# Power.net
KiCad netlist of a schematic drawn in Altium Designer
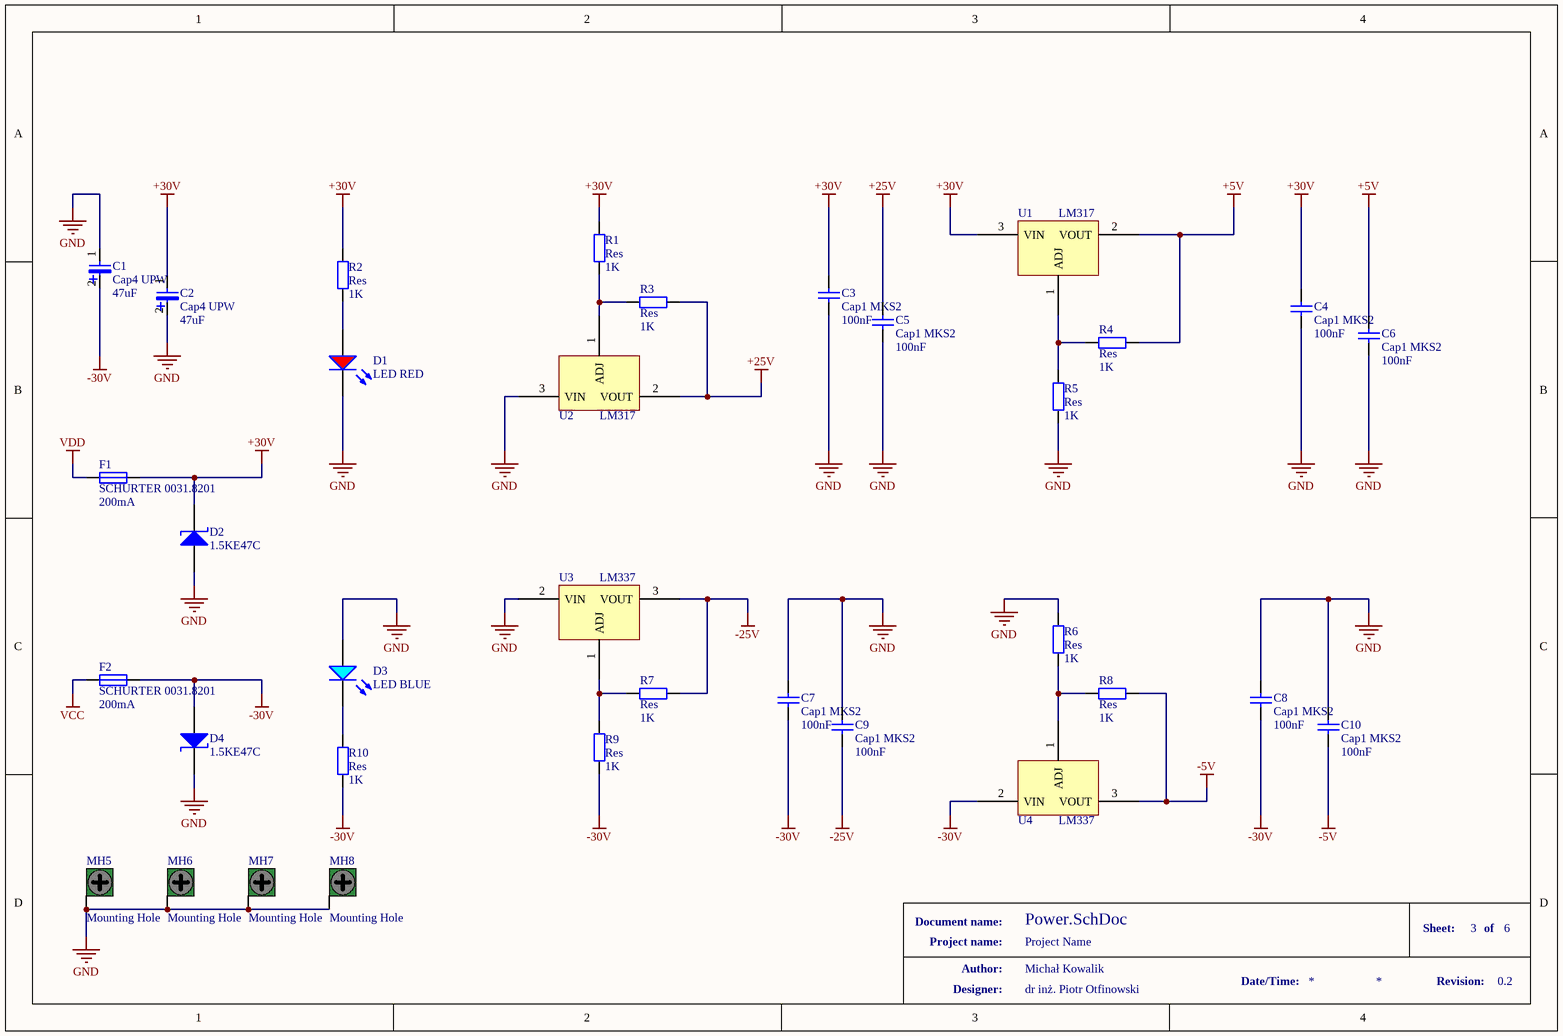
[diagram p0: Power.SchDoc]

(export (version "E")
  (design (tool "Eeschema 10.0.6"))
  (components
    (comp (ref "C1")
      (value "Cap4 UPW")
      (footprint "CAP-POLARISED-2MM")
      (description "Nichicon UPW Aluminium Electrolytic Capacitor")
      (fields (field (name "ALTIUM_VALUE") "47uF"))
      (libsource (lib "SchematicLib") (part "Cap4"))
    )
    (comp (ref "C2")
      (value "Cap4 UPW")
      (footprint "CAP-POLARISED-2MM")
      (description "Nichicon UPW Aluminium Electrolytic Capacitor")
      (fields (field (name "ALTIUM_VALUE") "47uF"))
      (libsource (lib "SchematicLib") (part "Cap4"))
    )
    (comp (ref "C3")
      (value "Cap1 MKS2")
      (footprint "CAP-0.5-WIMA_MKS2")
      (description "WIMA MKS2 Metallized Polyester (PET) \r\nCapacitors in PCM 5 mm")
      (fields (field (name "ALTIUM_VALUE") "100nF"))
      (libsource (lib "SchematicLib") (part "Cap1"))
    )
    (comp (ref "C4")
      (value "Cap1 MKS2")
      (footprint "CAP-0.5-WIMA_MKS2")
      (description "WIMA MKS2 Metallized Polyester (PET) \r\nCapacitors in PCM 5 mm")
      (fields (field (name "ALTIUM_VALUE") "100nF"))
      (libsource (lib "SchematicLib") (part "Cap1"))
    )
    (comp (ref "C5")
      (value "Cap1 MKS2")
      (footprint "CAP-0.5-WIMA_MKS2")
      (description "WIMA MKS2 Metallized Polyester (PET) \r\nCapacitors in PCM 5 mm")
      (fields (field (name "ALTIUM_VALUE") "100nF"))
      (libsource (lib "SchematicLib") (part "Cap1"))
    )
    (comp (ref "C6")
      (value "Cap1 MKS2")
      (footprint "CAP-0.5-WIMA_MKS2")
      (description "WIMA MKS2 Metallized Polyester (PET) \r\nCapacitors in PCM 5 mm")
      (fields (field (name "ALTIUM_VALUE") "100nF"))
      (libsource (lib "SchematicLib") (part "Cap1"))
    )
    (comp (ref "C7")
      (value "Cap1 MKS2")
      (footprint "CAP-0.5-WIMA_MKS2")
      (description "WIMA MKS2 Metallized Polyester (PET) \r\nCapacitors in PCM 5 mm")
      (fields (field (name "ALTIUM_VALUE") "100nF"))
      (libsource (lib "SchematicLib") (part "Cap1"))
    )
    (comp (ref "C8")
      (value "Cap1 MKS2")
      (footprint "CAP-0.5-WIMA_MKS2")
      (description "WIMA MKS2 Metallized Polyester (PET) \r\nCapacitors in PCM 5 mm")
      (fields (field (name "ALTIUM_VALUE") "100nF"))
      (libsource (lib "SchematicLib") (part "Cap1"))
    )
    (comp (ref "C9")
      (value "Cap1 MKS2")
      (footprint "CAP-0.5-WIMA_MKS2")
      (description "WIMA MKS2 Metallized Polyester (PET) \r\nCapacitors in PCM 5 mm")
      (fields (field (name "ALTIUM_VALUE") "100nF"))
      (libsource (lib "SchematicLib") (part "Cap1"))
    )
    (comp (ref "C10")
      (value "Cap1 MKS2")
      (footprint "CAP-0.5-WIMA_MKS2")
      (description "WIMA MKS2 Metallized Polyester (PET) \r\nCapacitors in PCM 5 mm")
      (fields (field (name "ALTIUM_VALUE") "100nF"))
      (libsource (lib "SchematicLib") (part "Cap1"))
    )
    (comp (ref "D1")
      (value "LED RED")
      (footprint "DIO_0805_IPC_MD")
      (description "Standard SMD 0805 Red LED")
      (fields (field (name "PUBLISHER") "Altium Limited"))
      (libsource (lib "SchematicLib") (part "LED RED"))
    )
    (comp (ref "D2")
      (value "1.5KE47C")
      (footprint "DIODE-0.7")
      (description "Transient Voltage Suppressor Diodes; Breakdown V: 44.7...49.4, Stand-off V: 40.2")
      (libsource (lib "SchematicLib") (part "1.5KE47C"))
    )
    (comp (ref "D3")
      (value "LED BLUE")
      (footprint "DIO_0805_IPC_MD")
      (description "Standard SMD 0805 Blue LED")
      (fields (field (name "PUBLISHER") "Altium Limited"))
      (libsource (lib "SchematicLib") (part "LED BLUE"))
    )
    (comp (ref "D4")
      (value "1.5KE47C")
      (footprint "DIODE-0.7")
      (description "Transient Voltage Suppressor Diodes; Breakdown V: 44.7...49.4, Stand-off V: 40.2")
      (libsource (lib "SchematicLib") (part "1.5KE47C"))
    )
    (comp (ref "F1")
      (value "SCHURTER 0031.8201")
      (footprint "SCHURTER 0031.8201")
      (description "Fuseholder Open Design, 5 x 20 mm, THT, SCHURTER 0031.8201")
      (fields (field (name "ALTIUM_VALUE") "200mA"))
      (libsource (lib "SchematicLib") (part "Fuse"))
    )
    (comp (ref "F2")
      (value "SCHURTER 0031.8201")
      (footprint "SCHURTER 0031.8201")
      (description "Fuseholder Open Design, 5 x 20 mm, THT, SCHURTER 0031.8201")
      (fields (field (name "ALTIUM_VALUE") "200mA"))
      (libsource (lib "SchematicLib") (part "Fuse"))
    )
    (comp (ref "MH5")
      (value "Mounting Hole")
      (footprint "agh_racing_2018:MOUNTING HOLE 3mm")
      (libsource (lib "SchematicLib") (part "Mounting Hole"))
    )
    (comp (ref "MH6")
      (value "Mounting Hole")
      (footprint "agh_racing_2018:MOUNTING HOLE 3mm")
      (libsource (lib "SchematicLib") (part "Mounting Hole"))
    )
    (comp (ref "MH7")
      (value "Mounting Hole")
      (footprint "agh_racing_2018:MOUNTING HOLE 3mm")
      (libsource (lib "SchematicLib") (part "Mounting Hole"))
    )
    (comp (ref "MH8")
      (value "Mounting Hole")
      (footprint "agh_racing_2018:MOUNTING HOLE 3mm")
      (libsource (lib "SchematicLib") (part "Mounting Hole"))
    )
    (comp (ref "R1")
      (value "Res")
      (footprint "RESISTOR-10mm")
      (description "Resistor")
      (fields (field (name "ALTIUM_VALUE") "1K"))
      (libsource (lib "SchematicLib") (part "Res"))
    )
    (comp (ref "R2")
      (value "Res")
      (footprint "RESISTOR-10mm")
      (description "Resistor")
      (fields (field (name "ALTIUM_VALUE") "1K"))
      (libsource (lib "SchematicLib") (part "Res"))
    )
    (comp (ref "R3")
      (value "Res")
      (footprint "RESISTOR-10mm")
      (description "Resistor")
      (fields (field (name "ALTIUM_VALUE") "1K"))
      (libsource (lib "") (part "Res_1"))
    )
    (comp (ref "R4")
      (value "Res")
      (footprint "RESISTOR-10mm")
      (description "Resistor")
      (fields (field (name "ALTIUM_VALUE") "1K"))
      (libsource (lib "") (part "Res_1"))
    )
    (comp (ref "R5")
      (value "Res")
      (footprint "RESISTOR-10mm")
      (description "Resistor")
      (fields (field (name "ALTIUM_VALUE") "1K"))
      (libsource (lib "SchematicLib") (part "Res"))
    )
    (comp (ref "R6")
      (value "Res")
      (footprint "RESISTOR-10mm")
      (description "Resistor")
      (fields (field (name "ALTIUM_VALUE") "1K"))
      (libsource (lib "") (part "Res_1"))
    )
    (comp (ref "R7")
      (value "Res")
      (footprint "RESISTOR-10mm")
      (description "Resistor")
      (fields (field (name "ALTIUM_VALUE") "1K"))
      (libsource (lib "") (part "Res_1"))
    )
    (comp (ref "R8")
      (value "Res")
      (footprint "RESISTOR-10mm")
      (description "Resistor")
      (fields (field (name "ALTIUM_VALUE") "1K"))
      (libsource (lib "") (part "Res_2"))
    )
    (comp (ref "R9")
      (value "Res")
      (footprint "RESISTOR-10mm")
      (description "Resistor")
      (fields (field (name "ALTIUM_VALUE") "1K"))
      (libsource (lib "SchematicLib") (part "Res"))
    )
    (comp (ref "R10")
      (value "Res")
      (footprint "RESISTOR-10mm")
      (description "Resistor")
      (fields (field (name "ALTIUM_VALUE") "1K"))
      (libsource (lib "") (part "Res_2"))
    )
    (comp (ref "U1")
      (value "LM317")
      (footprint "TO-220")
      (description "Wide Temperature Three-Pin Positive Adjustable Regulator")
      (libsource (lib "SchematicLib") (part "LM317"))
    )
    (comp (ref "U2")
      (value "LM317")
      (footprint "TO-220")
      (description "Wide Temperature Three-Pin Positive Adjustable Regulator")
      (libsource (lib "") (part "LM317_1"))
    )
    (comp (ref "U3")
      (value "LM337")
      (footprint "TO-220")
      (description "Wide Temperature Three-Pin Negative Adjustable Regulator")
      (libsource (lib "") (part "LM337_1"))
    )
    (comp (ref "U4")
      (value "LM337")
      (footprint "TO-220")
      (description "Wide Temperature Three-Pin Negative Adjustable Regulator")
      (libsource (lib "SchematicLib") (part "LM337"))
    )
  )
  (nets
    (net (code "1") (name "+5V") (class "Default")
      (node (ref "C6") (pin "2") (pinfunction "2_2") (pintype "passive"))
      (node (ref "R4") (pin "1") (pinfunction "1_1") (pintype "passive"))
      (node (ref "U1") (pin "2") (pinfunction "VOUT_2") (pintype "passive"))
    )
    (net (code "2") (name "+25V") (class "Default")
      (node (ref "C5") (pin "2") (pinfunction "2_2") (pintype "passive"))
      (node (ref "R3") (pin "1") (pinfunction "1_1") (pintype "passive"))
      (node (ref "U2") (pin "2") (pinfunction "VOUT_2") (pintype "passive"))
    )
    (net (code "3") (name "+30V") (class "Default")
      (node (ref "C2") (pin "1") (pinfunction "1_1") (pintype "passive"))
      (node (ref "C3") (pin "2") (pinfunction "2_2") (pintype "passive"))
      (node (ref "C4") (pin "2") (pinfunction "2_2") (pintype "passive"))
      (node (ref "D2") (pin "2") (pinfunction "IN2_2") (pintype "passive"))
      (node (ref "F1") (pin "2") (pinfunction "2_2") (pintype "passive"))
      (node (ref "R1") (pin "2") (pinfunction "2_2") (pintype "passive"))
      (node (ref "R2") (pin "2") (pinfunction "2_2") (pintype "passive"))
      (node (ref "U1") (pin "3") (pinfunction "VIN_3") (pintype "passive"))
    )
    (net (code "4") (name "-5V") (class "Default")
      (node (ref "C10") (pin "1") (pinfunction "1_1") (pintype "passive"))
      (node (ref "R8") (pin "1") (pinfunction "1_1") (pintype "passive"))
      (node (ref "U4") (pin "3") (pinfunction "VOUT_3") (pintype "passive"))
    )
    (net (code "5") (name "-25V") (class "Default")
      (node (ref "C9") (pin "1") (pinfunction "1_1") (pintype "passive"))
      (node (ref "R7") (pin "1") (pinfunction "1_1") (pintype "passive"))
      (node (ref "U3") (pin "3") (pinfunction "VOUT_3") (pintype "passive"))
    )
    (net (code "6") (name "-30V") (class "Default")
      (node (ref "C1") (pin "2") (pinfunction "2_2") (pintype "passive"))
      (node (ref "C7") (pin "1") (pinfunction "1_1") (pintype "passive"))
      (node (ref "C8") (pin "1") (pinfunction "1_1") (pintype "passive"))
      (node (ref "D4") (pin "1") (pinfunction "IN1_1") (pintype "passive"))
      (node (ref "F2") (pin "2") (pinfunction "2_2") (pintype "passive"))
      (node (ref "R10") (pin "2") (pinfunction "2_2") (pintype "passive"))
      (node (ref "R9") (pin "1") (pinfunction "1_1") (pintype "passive"))
      (node (ref "U4") (pin "2") (pinfunction "VIN_2") (pintype "passive"))
    )
    (net (code "7") (name "GND") (class "Default")
      (node (ref "C1") (pin "1") (pinfunction "1_1") (pintype "passive"))
      (node (ref "C10") (pin "2") (pinfunction "2_2") (pintype "passive"))
      (node (ref "C2") (pin "2") (pinfunction "2_2") (pintype "passive"))
      (node (ref "C3") (pin "1") (pinfunction "1_1") (pintype "passive"))
      (node (ref "C4") (pin "1") (pinfunction "1_1") (pintype "passive"))
      (node (ref "C5") (pin "1") (pinfunction "1_1") (pintype "passive"))
      (node (ref "C6") (pin "1") (pinfunction "1_1") (pintype "passive"))
      (node (ref "C7") (pin "2") (pinfunction "2_2") (pintype "passive"))
      (node (ref "C8") (pin "2") (pinfunction "2_2") (pintype "passive"))
      (node (ref "C9") (pin "2") (pinfunction "2_2") (pintype "passive"))
      (node (ref "D1") (pin "2") (pinfunction "K_2") (pintype "passive"))
      (node (ref "D2") (pin "1") (pinfunction "IN1_1") (pintype "passive"))
      (node (ref "D3") (pin "1") (pinfunction "A_1") (pintype "passive"))
      (node (ref "D4") (pin "2") (pinfunction "IN2_2") (pintype "passive"))
      (node (ref "MH5") (pin "MOUNTING") (pinfunction "MOUNTING_MOUNTING") (pintype "passive"))
      (node (ref "MH6") (pin "MOUNTING") (pinfunction "MOUNTING_MOUNTING") (pintype "passive"))
      (node (ref "MH7") (pin "MOUNTING") (pinfunction "MOUNTING_MOUNTING") (pintype "passive"))
      (node (ref "MH8") (pin "MOUNTING") (pinfunction "MOUNTING_MOUNTING") (pintype "passive"))
      (node (ref "R5") (pin "1") (pinfunction "1_1") (pintype "passive"))
      (node (ref "R6") (pin "1") (pinfunction "1_1") (pintype "passive"))
      (node (ref "U2") (pin "3") (pinfunction "VIN_3") (pintype "passive"))
      (node (ref "U3") (pin "2") (pinfunction "VIN_2") (pintype "passive"))
    )
    (net (code "8") (name "Net-(D1-A)") (class "Default")
      (node (ref "D1") (pin "1") (pinfunction "A_1") (pintype "passive"))
      (node (ref "R2") (pin "1") (pinfunction "1_1") (pintype "passive"))
    )
    (net (code "9") (name "Net-(D3-K)") (class "Default")
      (node (ref "D3") (pin "2") (pinfunction "K_2") (pintype "passive"))
      (node (ref "R10") (pin "1") (pinfunction "1_1") (pintype "passive"))
    )
    (net (code "10") (name "Net-(U1-ADJ)") (class "Default")
      (node (ref "R4") (pin "2") (pinfunction "2_2") (pintype "passive"))
      (node (ref "R5") (pin "2") (pinfunction "2_2") (pintype "passive"))
      (node (ref "U1") (pin "1") (pinfunction "ADJ_1") (pintype "passive"))
    )
    (net (code "11") (name "Net-(U2-ADJ)") (class "Default")
      (node (ref "R1") (pin "1") (pinfunction "1_1") (pintype "passive"))
      (node (ref "R3") (pin "2") (pinfunction "2_2") (pintype "passive"))
      (node (ref "U2") (pin "1") (pinfunction "ADJ_1") (pintype "passive"))
    )
    (net (code "12") (name "Net-(U3-ADJ)") (class "Default")
      (node (ref "R7") (pin "2") (pinfunction "2_2") (pintype "passive"))
      (node (ref "R9") (pin "2") (pinfunction "2_2") (pintype "passive"))
      (node (ref "U3") (pin "1") (pinfunction "ADJ_1") (pintype "passive"))
    )
    (net (code "13") (name "Net-(U4-ADJ)") (class "Default")
      (node (ref "R6") (pin "2") (pinfunction "2_2") (pintype "passive"))
      (node (ref "R8") (pin "2") (pinfunction "2_2") (pintype "passive"))
      (node (ref "U4") (pin "1") (pinfunction "ADJ_1") (pintype "passive"))
    )
    (net (code "14") (name "VCC") (class "Default")
      (node (ref "F2") (pin "1") (pinfunction "1_1") (pintype "passive"))
    )
    (net (code "15") (name "VDD") (class "Default")
      (node (ref "F1") (pin "1") (pinfunction "1_1") (pintype "passive"))
    )
  )
)
